# DI_220V_DC.net
KiCad netlist of a schematic drawn in Altium Designer
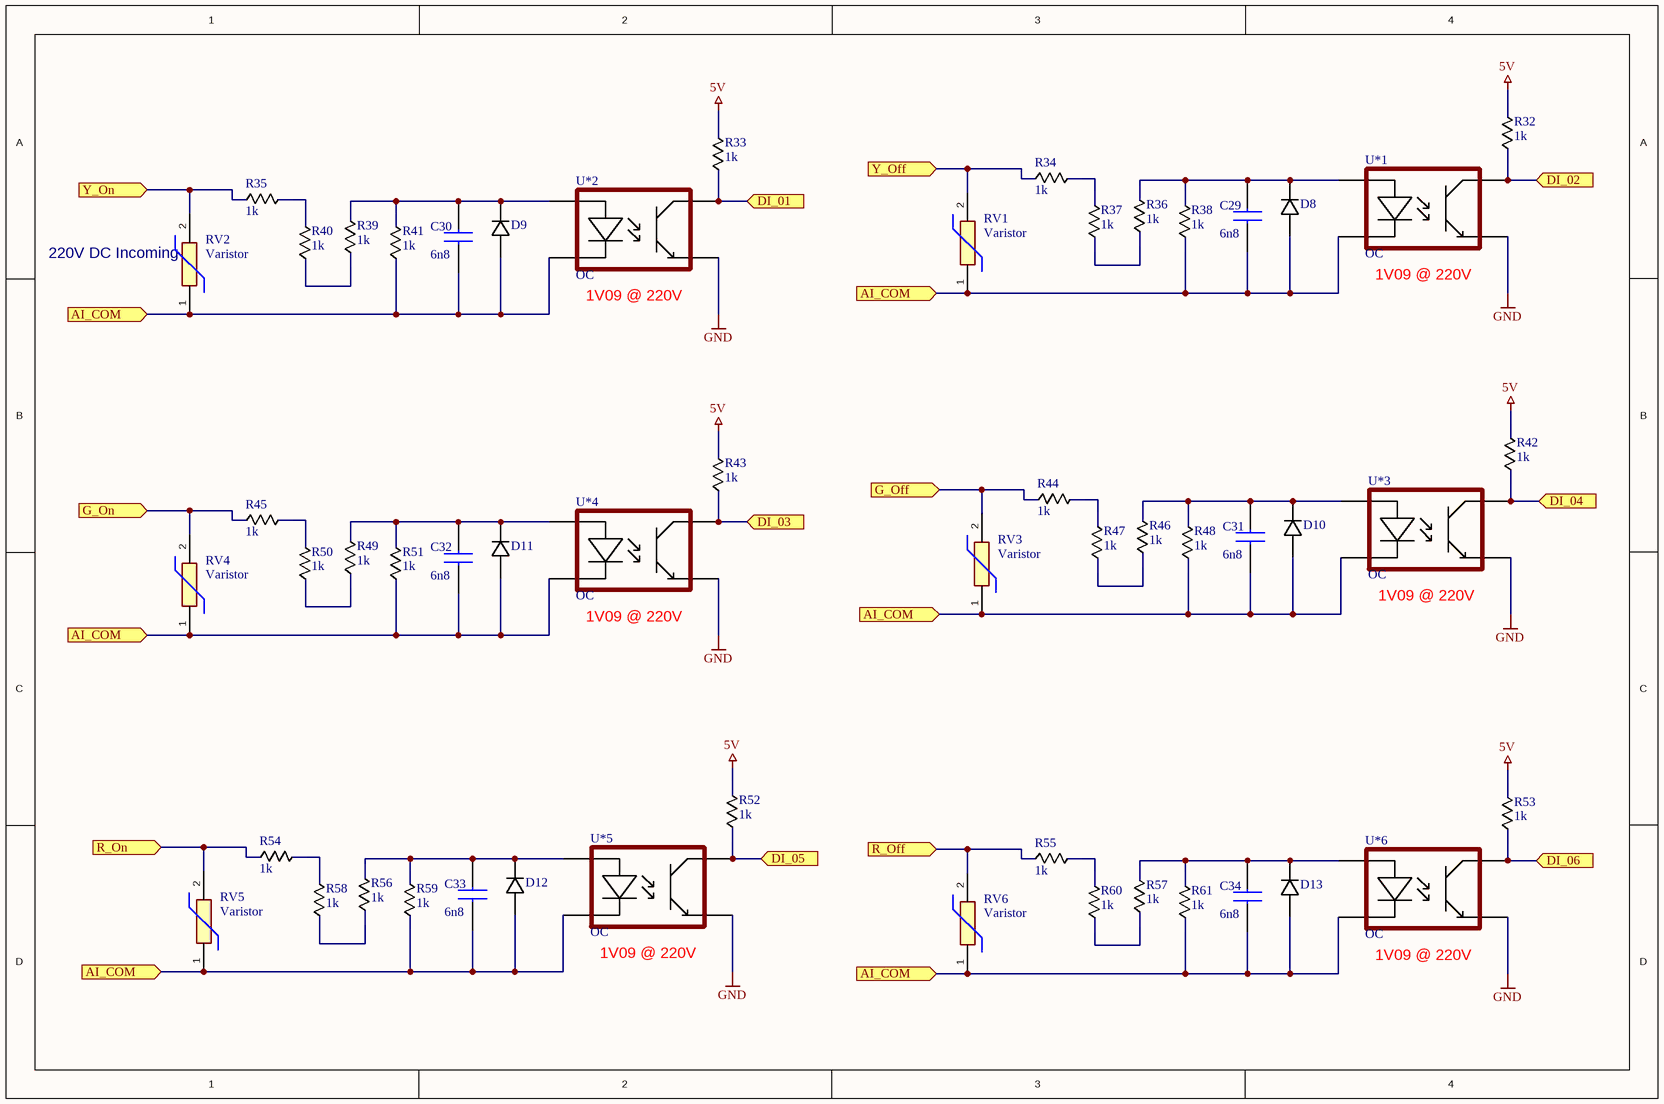
[diagram p0: DI 220V DC.SchDoc]

(export (version "E")
  (design (tool "Eeschema 10.0.6"))
  (components
    (comp (ref "C29")
      (value "6n8")
      (footprint "0603 CAP")
      (description "GRM188R71H682MA01D")
      (fields
        (field (name "MANUFACTURER_PART_NUMBER") "GRM188R72A103KA01D")
        (field (name "MOUSER PART NUMBER") "81-GRM188R72A103KA1D")
      )
      (libsource (lib "IGAS Elements") (part "0603 CAP"))
    )
    (comp (ref "C30")
      (value "6n8")
      (footprint "0603 CAP")
      (description "GRM188R71H682MA01D")
      (fields
        (field (name "MANUFACTURER_PART_NUMBER") "GRM188R72A103KA01D")
        (field (name "MOUSER PART NUMBER") "81-GRM188R72A103KA1D")
      )
      (libsource (lib "IGAS Elements") (part "0603 CAP"))
    )
    (comp (ref "C31")
      (value "6n8")
      (footprint "0603 CAP")
      (description "GRM188R71H682MA01D")
      (fields
        (field (name "MANUFACTURER_PART_NUMBER") "GRM188R72A103KA01D")
        (field (name "MOUSER PART NUMBER") "81-GRM188R72A103KA1D")
      )
      (libsource (lib "IGAS Elements") (part "0603 CAP"))
    )
    (comp (ref "C32")
      (value "6n8")
      (footprint "0603 CAP")
      (description "GRM188R71H682MA01D")
      (fields
        (field (name "MANUFACTURER_PART_NUMBER") "GRM188R72A103KA01D")
        (field (name "MOUSER PART NUMBER") "81-GRM188R72A103KA1D")
      )
      (libsource (lib "IGAS Elements") (part "0603 CAP"))
    )
    (comp (ref "C33")
      (value "6n8")
      (footprint "0603 CAP")
      (description "GRM188R71H682MA01D")
      (fields
        (field (name "MANUFACTURER_PART_NUMBER") "GRM188R72A103KA01D")
        (field (name "MOUSER PART NUMBER") "81-GRM188R72A103KA1D")
      )
      (libsource (lib "IGAS Elements") (part "0603 CAP"))
    )
    (comp (ref "C34")
      (value "6n8")
      (footprint "0603 CAP")
      (description "GRM188R71H682MA01D")
      (fields
        (field (name "MANUFACTURER_PART_NUMBER") "GRM188R72A103KA01D")
        (field (name "MOUSER PART NUMBER") "81-GRM188R72A103KA1D")
      )
      (libsource (lib "IGAS Elements") (part "0603 CAP"))
    )
    (comp (ref "D8")
      (value "Diode_1")
      (footprint "SOD-323 (SC-76) - Reflow")
      (description "1N4148WS")
      (libsource (lib "IGAS Elements") (part "Diode_1"))
    )
    (comp (ref "D9")
      (value "Diode_1")
      (footprint "SOD-323 (SC-76) - Reflow")
      (description "1N4148WS")
      (libsource (lib "IGAS Elements") (part "Diode_1"))
    )
    (comp (ref "D10")
      (value "Diode_1")
      (footprint "SOD-323 (SC-76) - Reflow")
      (description "1N4148WS")
      (libsource (lib "IGAS Elements") (part "Diode_1"))
    )
    (comp (ref "D11")
      (value "Diode_1")
      (footprint "SOD-323 (SC-76) - Reflow")
      (description "1N4148WS")
      (libsource (lib "IGAS Elements") (part "Diode_1"))
    )
    (comp (ref "D12")
      (value "Diode_1")
      (footprint "SOD-323 (SC-76) - Reflow")
      (description "1N4148WS")
      (libsource (lib "IGAS Elements") (part "Diode_1"))
    )
    (comp (ref "D13")
      (value "Diode_1")
      (footprint "SOD-323 (SC-76) - Reflow")
      (description "1N4148WS")
      (libsource (lib "IGAS Elements") (part "Diode_1"))
    )
    (comp (ref "R32") (value "1k") (footprint "0603 CAP") (libsource (lib "IGAS Elements") (part "0603 RES")))
    (comp (ref "R33") (value "1k") (footprint "0603 CAP") (libsource (lib "IGAS Elements") (part "0603 RES")))
    (comp (ref "R34") (value "1k") (footprint "1206 Res") (libsource (lib "IGAS Elements") (part "1206 RES")))
    (comp (ref "R35") (value "1k") (footprint "1206 Res") (libsource (lib "IGAS Elements") (part "1206 RES")))
    (comp (ref "R36") (value "1k") (footprint "1206 Res") (libsource (lib "IGAS Elements") (part "1206 RES")))
    (comp (ref "R37") (value "1k") (footprint "1206 Res") (libsource (lib "IGAS Elements") (part "1206 RES")))
    (comp (ref "R38") (value "1k") (footprint "1206 Res") (libsource (lib "IGAS Elements") (part "1206 RES")))
    (comp (ref "R39") (value "1k") (footprint "1206 Res") (libsource (lib "IGAS Elements") (part "1206 RES")))
    (comp (ref "R40") (value "1k") (footprint "1206 Res") (libsource (lib "IGAS Elements") (part "1206 RES")))
    (comp (ref "R41") (value "1k") (footprint "1206 Res") (libsource (lib "IGAS Elements") (part "1206 RES")))
    (comp (ref "R42") (value "1k") (footprint "0603 CAP") (libsource (lib "IGAS Elements") (part "0603 RES")))
    (comp (ref "R43") (value "1k") (footprint "0603 CAP") (libsource (lib "IGAS Elements") (part "0603 RES")))
    (comp (ref "R44") (value "1k") (footprint "1206 Res") (libsource (lib "IGAS Elements") (part "1206 RES")))
    (comp (ref "R45") (value "1k") (footprint "1206 Res") (libsource (lib "IGAS Elements") (part "1206 RES")))
    (comp (ref "R46") (value "1k") (footprint "1206 Res") (libsource (lib "IGAS Elements") (part "1206 RES")))
    (comp (ref "R47") (value "1k") (footprint "1206 Res") (libsource (lib "IGAS Elements") (part "1206 RES")))
    (comp (ref "R48") (value "1k") (footprint "1206 Res") (libsource (lib "IGAS Elements") (part "1206 RES")))
    (comp (ref "R49") (value "1k") (footprint "1206 Res") (libsource (lib "IGAS Elements") (part "1206 RES")))
    (comp (ref "R50") (value "1k") (footprint "1206 Res") (libsource (lib "IGAS Elements") (part "1206 RES")))
    (comp (ref "R51") (value "1k") (footprint "1206 Res") (libsource (lib "IGAS Elements") (part "1206 RES")))
    (comp (ref "R52") (value "1k") (footprint "0603 CAP") (libsource (lib "IGAS Elements") (part "0603 RES")))
    (comp (ref "R53") (value "1k") (footprint "0603 CAP") (libsource (lib "IGAS Elements") (part "0603 RES")))
    (comp (ref "R54") (value "1k") (footprint "1206 Res") (libsource (lib "IGAS Elements") (part "1206 RES")))
    (comp (ref "R55") (value "1k") (footprint "1206 Res") (libsource (lib "IGAS Elements") (part "1206 RES")))
    (comp (ref "R56") (value "1k") (footprint "1206 Res") (libsource (lib "IGAS Elements") (part "1206 RES")))
    (comp (ref "R57") (value "1k") (footprint "1206 Res") (libsource (lib "IGAS Elements") (part "1206 RES")))
    (comp (ref "R58") (value "1k") (footprint "1206 Res") (libsource (lib "IGAS Elements") (part "1206 RES")))
    (comp (ref "R59") (value "1k") (footprint "1206 Res") (libsource (lib "IGAS Elements") (part "1206 RES")))
    (comp (ref "R60") (value "1k") (footprint "1206 Res") (libsource (lib "IGAS Elements") (part "1206 RES")))
    (comp (ref "R61") (value "1k") (footprint "1206 Res") (libsource (lib "IGAS Elements") (part "1206 RES")))
    (comp (ref "RV1")
      (value "Varistor")
      (footprint "IGAS Elements:S10K275")
      (description "B72210-S 271-K101")
      (fields
        (field (name "MANUFACTURER_PART_NUMBER") "B72210S0271K101")
        (field (name "MOUSER PART NUMBER") "871-B72210S271K101")
      )
      (libsource (lib "IGAS Elements") (part "B72210S0271K101"))
    )
    (comp (ref "RV2")
      (value "Varistor")
      (footprint "IGAS Elements:S10K275")
      (description "B72210-S 271-K101")
      (fields
        (field (name "MANUFACTURER_PART_NUMBER") "B72210S0271K101")
        (field (name "MOUSER PART NUMBER") "871-B72210S271K101")
      )
      (libsource (lib "IGAS Elements") (part "B72210S0271K101"))
    )
    (comp (ref "RV3")
      (value "Varistor")
      (footprint "IGAS Elements:S10K275")
      (description "B72210-S 271-K101")
      (fields
        (field (name "MANUFACTURER_PART_NUMBER") "B72210S0271K101")
        (field (name "MOUSER PART NUMBER") "871-B72210S271K101")
      )
      (libsource (lib "IGAS Elements") (part "B72210S0271K101"))
    )
    (comp (ref "RV4")
      (value "Varistor")
      (footprint "IGAS Elements:S10K275")
      (description "B72210-S 271-K101")
      (fields
        (field (name "MANUFACTURER_PART_NUMBER") "B72210S0271K101")
        (field (name "MOUSER PART NUMBER") "871-B72210S271K101")
      )
      (libsource (lib "IGAS Elements") (part "B72210S0271K101"))
    )
    (comp (ref "RV5")
      (value "Varistor")
      (footprint "IGAS Elements:S10K275")
      (description "B72210-S 271-K101")
      (fields
        (field (name "MANUFACTURER_PART_NUMBER") "B72210S0271K101")
        (field (name "MOUSER PART NUMBER") "871-B72210S271K101")
      )
      (libsource (lib "IGAS Elements") (part "B72210S0271K101"))
    )
    (comp (ref "RV6")
      (value "Varistor")
      (footprint "IGAS Elements:S10K275")
      (description "B72210-S 271-K101")
      (fields
        (field (name "MANUFACTURER_PART_NUMBER") "B72210S0271K101")
        (field (name "MOUSER PART NUMBER") "871-B72210S271K101")
      )
      (libsource (lib "IGAS Elements") (part "B72210S0271K101"))
    )
    (comp (ref "U*1")
      (value "OC")
      (footprint "IGAS Elements:LTV-357T")
      (description "LTV-357T")
      (libsource (lib "IGAS Elements") (part "LTV-357T"))
    )
    (comp (ref "U*2")
      (value "OC")
      (footprint "IGAS Elements:LTV-357T")
      (description "LTV-357T")
      (libsource (lib "IGAS Elements") (part "LTV-357T"))
    )
    (comp (ref "U*3")
      (value "OC")
      (footprint "IGAS Elements:LTV-357T")
      (description "LTV-357T")
      (libsource (lib "IGAS Elements") (part "LTV-357T"))
    )
    (comp (ref "U*4")
      (value "OC")
      (footprint "IGAS Elements:LTV-357T")
      (description "LTV-357T")
      (libsource (lib "IGAS Elements") (part "LTV-357T"))
    )
    (comp (ref "U*5")
      (value "OC")
      (footprint "IGAS Elements:LTV-357T")
      (description "LTV-357T")
      (libsource (lib "IGAS Elements") (part "LTV-357T"))
    )
    (comp (ref "U*6")
      (value "OC")
      (footprint "IGAS Elements:LTV-357T")
      (description "LTV-357T")
      (libsource (lib "IGAS Elements") (part "LTV-357T"))
    )
  )
  (nets
    (net (code "1") (name "/AI_COM") (class "Default")
      (node (ref "C29") (pin "1") (pinfunction "1_1") (pintype "passive"))
      (node (ref "C30") (pin "1") (pinfunction "1_1") (pintype "passive"))
      (node (ref "C31") (pin "1") (pinfunction "1_1") (pintype "passive"))
      (node (ref "C32") (pin "1") (pinfunction "1_1") (pintype "passive"))
      (node (ref "C33") (pin "1") (pinfunction "1_1") (pintype "passive"))
      (node (ref "C34") (pin "1") (pinfunction "1_1") (pintype "passive"))
      (node (ref "D10") (pin "2") (pinfunction "A_2") (pintype "passive"))
      (node (ref "D11") (pin "2") (pinfunction "A_2") (pintype "passive"))
      (node (ref "D12") (pin "2") (pinfunction "A_2") (pintype "passive"))
      (node (ref "D13") (pin "2") (pinfunction "A_2") (pintype "passive"))
      (node (ref "D8") (pin "2") (pinfunction "A_2") (pintype "passive"))
      (node (ref "D9") (pin "2") (pinfunction "A_2") (pintype "passive"))
      (node (ref "R38") (pin "1") (pintype "passive"))
      (node (ref "R41") (pin "1") (pintype "passive"))
      (node (ref "R48") (pin "1") (pintype "passive"))
      (node (ref "R51") (pin "1") (pintype "passive"))
      (node (ref "R59") (pin "1") (pintype "passive"))
      (node (ref "R61") (pin "1") (pintype "passive"))
      (node (ref "RV1") (pin "1") (pinfunction "1_1") (pintype "passive"))
      (node (ref "RV2") (pin "1") (pinfunction "1_1") (pintype "passive"))
      (node (ref "RV3") (pin "1") (pinfunction "1_1") (pintype "passive"))
      (node (ref "RV4") (pin "1") (pinfunction "1_1") (pintype "passive"))
      (node (ref "RV5") (pin "1") (pinfunction "1_1") (pintype "passive"))
      (node (ref "RV6") (pin "1") (pinfunction "1_1") (pintype "passive"))
      (node (ref "U*1") (pin "Cathode") (pinfunction "C_Cathode") (pintype "passive"))
      (node (ref "U*2") (pin "Cathode") (pinfunction "C_Cathode") (pintype "passive"))
      (node (ref "U*3") (pin "Cathode") (pinfunction "C_Cathode") (pintype "passive"))
      (node (ref "U*4") (pin "Cathode") (pinfunction "C_Cathode") (pintype "passive"))
      (node (ref "U*5") (pin "Cathode") (pinfunction "C_Cathode") (pintype "passive"))
      (node (ref "U*6") (pin "Cathode") (pinfunction "C_Cathode") (pintype "passive"))
    )
    (net (code "2") (name "/DI_01") (class "Default")
      (node (ref "R33") (pin "1") (pintype "passive"))
      (node (ref "U*2") (pin "Collector") (pinfunction "C_Collector") (pintype "passive"))
    )
    (net (code "3") (name "/DI_02") (class "Default")
      (node (ref "R32") (pin "1") (pintype "passive"))
      (node (ref "U*1") (pin "Collector") (pinfunction "C_Collector") (pintype "passive"))
    )
    (net (code "4") (name "/DI_03") (class "Default")
      (node (ref "R43") (pin "1") (pintype "passive"))
      (node (ref "U*4") (pin "Collector") (pinfunction "C_Collector") (pintype "passive"))
    )
    (net (code "5") (name "/DI_04") (class "Default")
      (node (ref "R42") (pin "1") (pintype "passive"))
      (node (ref "U*3") (pin "Collector") (pinfunction "C_Collector") (pintype "passive"))
    )
    (net (code "6") (name "/DI_05") (class "Default")
      (node (ref "R52") (pin "1") (pintype "passive"))
      (node (ref "U*5") (pin "Collector") (pinfunction "C_Collector") (pintype "passive"))
    )
    (net (code "7") (name "/DI_06") (class "Default")
      (node (ref "R53") (pin "1") (pintype "passive"))
      (node (ref "U*6") (pin "Collector") (pinfunction "C_Collector") (pintype "passive"))
    )
    (net (code "8") (name "/G_Off") (class "Default")
      (node (ref "R44") (pin "1") (pintype "passive"))
      (node (ref "RV3") (pin "2") (pinfunction "2_2") (pintype "passive"))
    )
    (net (code "9") (name "/G_On") (class "Default")
      (node (ref "R45") (pin "1") (pintype "passive"))
      (node (ref "RV4") (pin "2") (pinfunction "2_2") (pintype "passive"))
    )
    (net (code "10") (name "/R_Off") (class "Default")
      (node (ref "R55") (pin "1") (pintype "passive"))
      (node (ref "RV6") (pin "2") (pinfunction "2_2") (pintype "passive"))
    )
    (net (code "11") (name "/R_On") (class "Default")
      (node (ref "R54") (pin "1") (pintype "passive"))
      (node (ref "RV5") (pin "2") (pinfunction "2_2") (pintype "passive"))
    )
    (net (code "12") (name "/Y_Off") (class "Default")
      (node (ref "R34") (pin "1") (pintype "passive"))
      (node (ref "RV1") (pin "2") (pinfunction "2_2") (pintype "passive"))
    )
    (net (code "13") (name "/Y_On") (class "Default")
      (node (ref "R35") (pin "1") (pintype "passive"))
      (node (ref "RV2") (pin "2") (pinfunction "2_2") (pintype "passive"))
    )
    (net (code "14") (name "5V") (class "Default")
      (node (ref "R32") (pin "2") (pintype "passive"))
      (node (ref "R33") (pin "2") (pintype "passive"))
      (node (ref "R42") (pin "2") (pintype "passive"))
      (node (ref "R43") (pin "2") (pintype "passive"))
      (node (ref "R52") (pin "2") (pintype "passive"))
      (node (ref "R53") (pin "2") (pintype "passive"))
    )
    (net (code "15") (name "GND") (class "Default")
      (node (ref "U*1") (pin "Emmiter") (pinfunction "E_Emmiter") (pintype "passive"))
      (node (ref "U*2") (pin "Emmiter") (pinfunction "E_Emmiter") (pintype "passive"))
      (node (ref "U*3") (pin "Emmiter") (pinfunction "E_Emmiter") (pintype "passive"))
      (node (ref "U*4") (pin "Emmiter") (pinfunction "E_Emmiter") (pintype "passive"))
      (node (ref "U*5") (pin "Emmiter") (pinfunction "E_Emmiter") (pintype "passive"))
      (node (ref "U*6") (pin "Emmiter") (pinfunction "E_Emmiter") (pintype "passive"))
    )
    (net (code "16") (name "Net-(D8-C)") (class "Default")
      (node (ref "C29") (pin "2") (pinfunction "2_2") (pintype "passive"))
      (node (ref "D8") (pin "1") (pinfunction "C_1") (pintype "passive"))
      (node (ref "R36") (pin "2") (pintype "passive"))
      (node (ref "R38") (pin "2") (pintype "passive"))
      (node (ref "U*1") (pin "Anode") (pinfunction "A_Anode") (pintype "passive"))
    )
    (net (code "17") (name "Net-(D9-C)") (class "Default")
      (node (ref "C30") (pin "2") (pinfunction "2_2") (pintype "passive"))
      (node (ref "D9") (pin "1") (pinfunction "C_1") (pintype "passive"))
      (node (ref "R39") (pin "2") (pintype "passive"))
      (node (ref "R41") (pin "2") (pintype "passive"))
      (node (ref "U*2") (pin "Anode") (pinfunction "A_Anode") (pintype "passive"))
    )
    (net (code "18") (name "Net-(D10-C)") (class "Default")
      (node (ref "C31") (pin "2") (pinfunction "2_2") (pintype "passive"))
      (node (ref "D10") (pin "1") (pinfunction "C_1") (pintype "passive"))
      (node (ref "R46") (pin "2") (pintype "passive"))
      (node (ref "R48") (pin "2") (pintype "passive"))
      (node (ref "U*3") (pin "Anode") (pinfunction "A_Anode") (pintype "passive"))
    )
    (net (code "19") (name "Net-(D11-C)") (class "Default")
      (node (ref "C32") (pin "2") (pinfunction "2_2") (pintype "passive"))
      (node (ref "D11") (pin "1") (pinfunction "C_1") (pintype "passive"))
      (node (ref "R49") (pin "2") (pintype "passive"))
      (node (ref "R51") (pin "2") (pintype "passive"))
      (node (ref "U*4") (pin "Anode") (pinfunction "A_Anode") (pintype "passive"))
    )
    (net (code "20") (name "Net-(D12-C)") (class "Default")
      (node (ref "C33") (pin "2") (pinfunction "2_2") (pintype "passive"))
      (node (ref "D12") (pin "1") (pinfunction "C_1") (pintype "passive"))
      (node (ref "R56") (pin "2") (pintype "passive"))
      (node (ref "R59") (pin "2") (pintype "passive"))
      (node (ref "U*5") (pin "Anode") (pinfunction "A_Anode") (pintype "passive"))
    )
    (net (code "21") (name "Net-(D13-C)") (class "Default")
      (node (ref "C34") (pin "2") (pinfunction "2_2") (pintype "passive"))
      (node (ref "D13") (pin "1") (pinfunction "C_1") (pintype "passive"))
      (node (ref "R57") (pin "2") (pintype "passive"))
      (node (ref "R61") (pin "2") (pintype "passive"))
      (node (ref "U*6") (pin "Anode") (pinfunction "A_Anode") (pintype "passive"))
    )
    (net (code "22") (name "Net-(R34-Pad2)") (class "Default")
      (node (ref "R34") (pin "2") (pintype "passive"))
      (node (ref "R37") (pin "2") (pintype "passive"))
    )
    (net (code "23") (name "Net-(R35-Pad2)") (class "Default")
      (node (ref "R35") (pin "2") (pintype "passive"))
      (node (ref "R40") (pin "2") (pintype "passive"))
    )
    (net (code "24") (name "Net-(R36-Pad1)") (class "Default")
      (node (ref "R36") (pin "1") (pintype "passive"))
      (node (ref "R37") (pin "1") (pintype "passive"))
    )
    (net (code "25") (name "Net-(R39-Pad1)") (class "Default")
      (node (ref "R39") (pin "1") (pintype "passive"))
      (node (ref "R40") (pin "1") (pintype "passive"))
    )
    (net (code "26") (name "Net-(R44-Pad2)") (class "Default")
      (node (ref "R44") (pin "2") (pintype "passive"))
      (node (ref "R47") (pin "2") (pintype "passive"))
    )
    (net (code "27") (name "Net-(R45-Pad2)") (class "Default")
      (node (ref "R45") (pin "2") (pintype "passive"))
      (node (ref "R50") (pin "2") (pintype "passive"))
    )
    (net (code "28") (name "Net-(R46-Pad1)") (class "Default")
      (node (ref "R46") (pin "1") (pintype "passive"))
      (node (ref "R47") (pin "1") (pintype "passive"))
    )
    (net (code "29") (name "Net-(R49-Pad1)") (class "Default")
      (node (ref "R49") (pin "1") (pintype "passive"))
      (node (ref "R50") (pin "1") (pintype "passive"))
    )
    (net (code "30") (name "Net-(R54-Pad2)") (class "Default")
      (node (ref "R54") (pin "2") (pintype "passive"))
      (node (ref "R58") (pin "2") (pintype "passive"))
    )
    (net (code "31") (name "Net-(R55-Pad2)") (class "Default")
      (node (ref "R55") (pin "2") (pintype "passive"))
      (node (ref "R60") (pin "2") (pintype "passive"))
    )
    (net (code "32") (name "Net-(R56-Pad1)") (class "Default")
      (node (ref "R56") (pin "1") (pintype "passive"))
      (node (ref "R58") (pin "1") (pintype "passive"))
    )
    (net (code "33") (name "Net-(R57-Pad1)") (class "Default")
      (node (ref "R57") (pin "1") (pintype "passive"))
      (node (ref "R60") (pin "1") (pintype "passive"))
    )
  )
)
